# MGT_Banks_115-116.net
KiCad netlist of a schematic drawn in Altium Designer
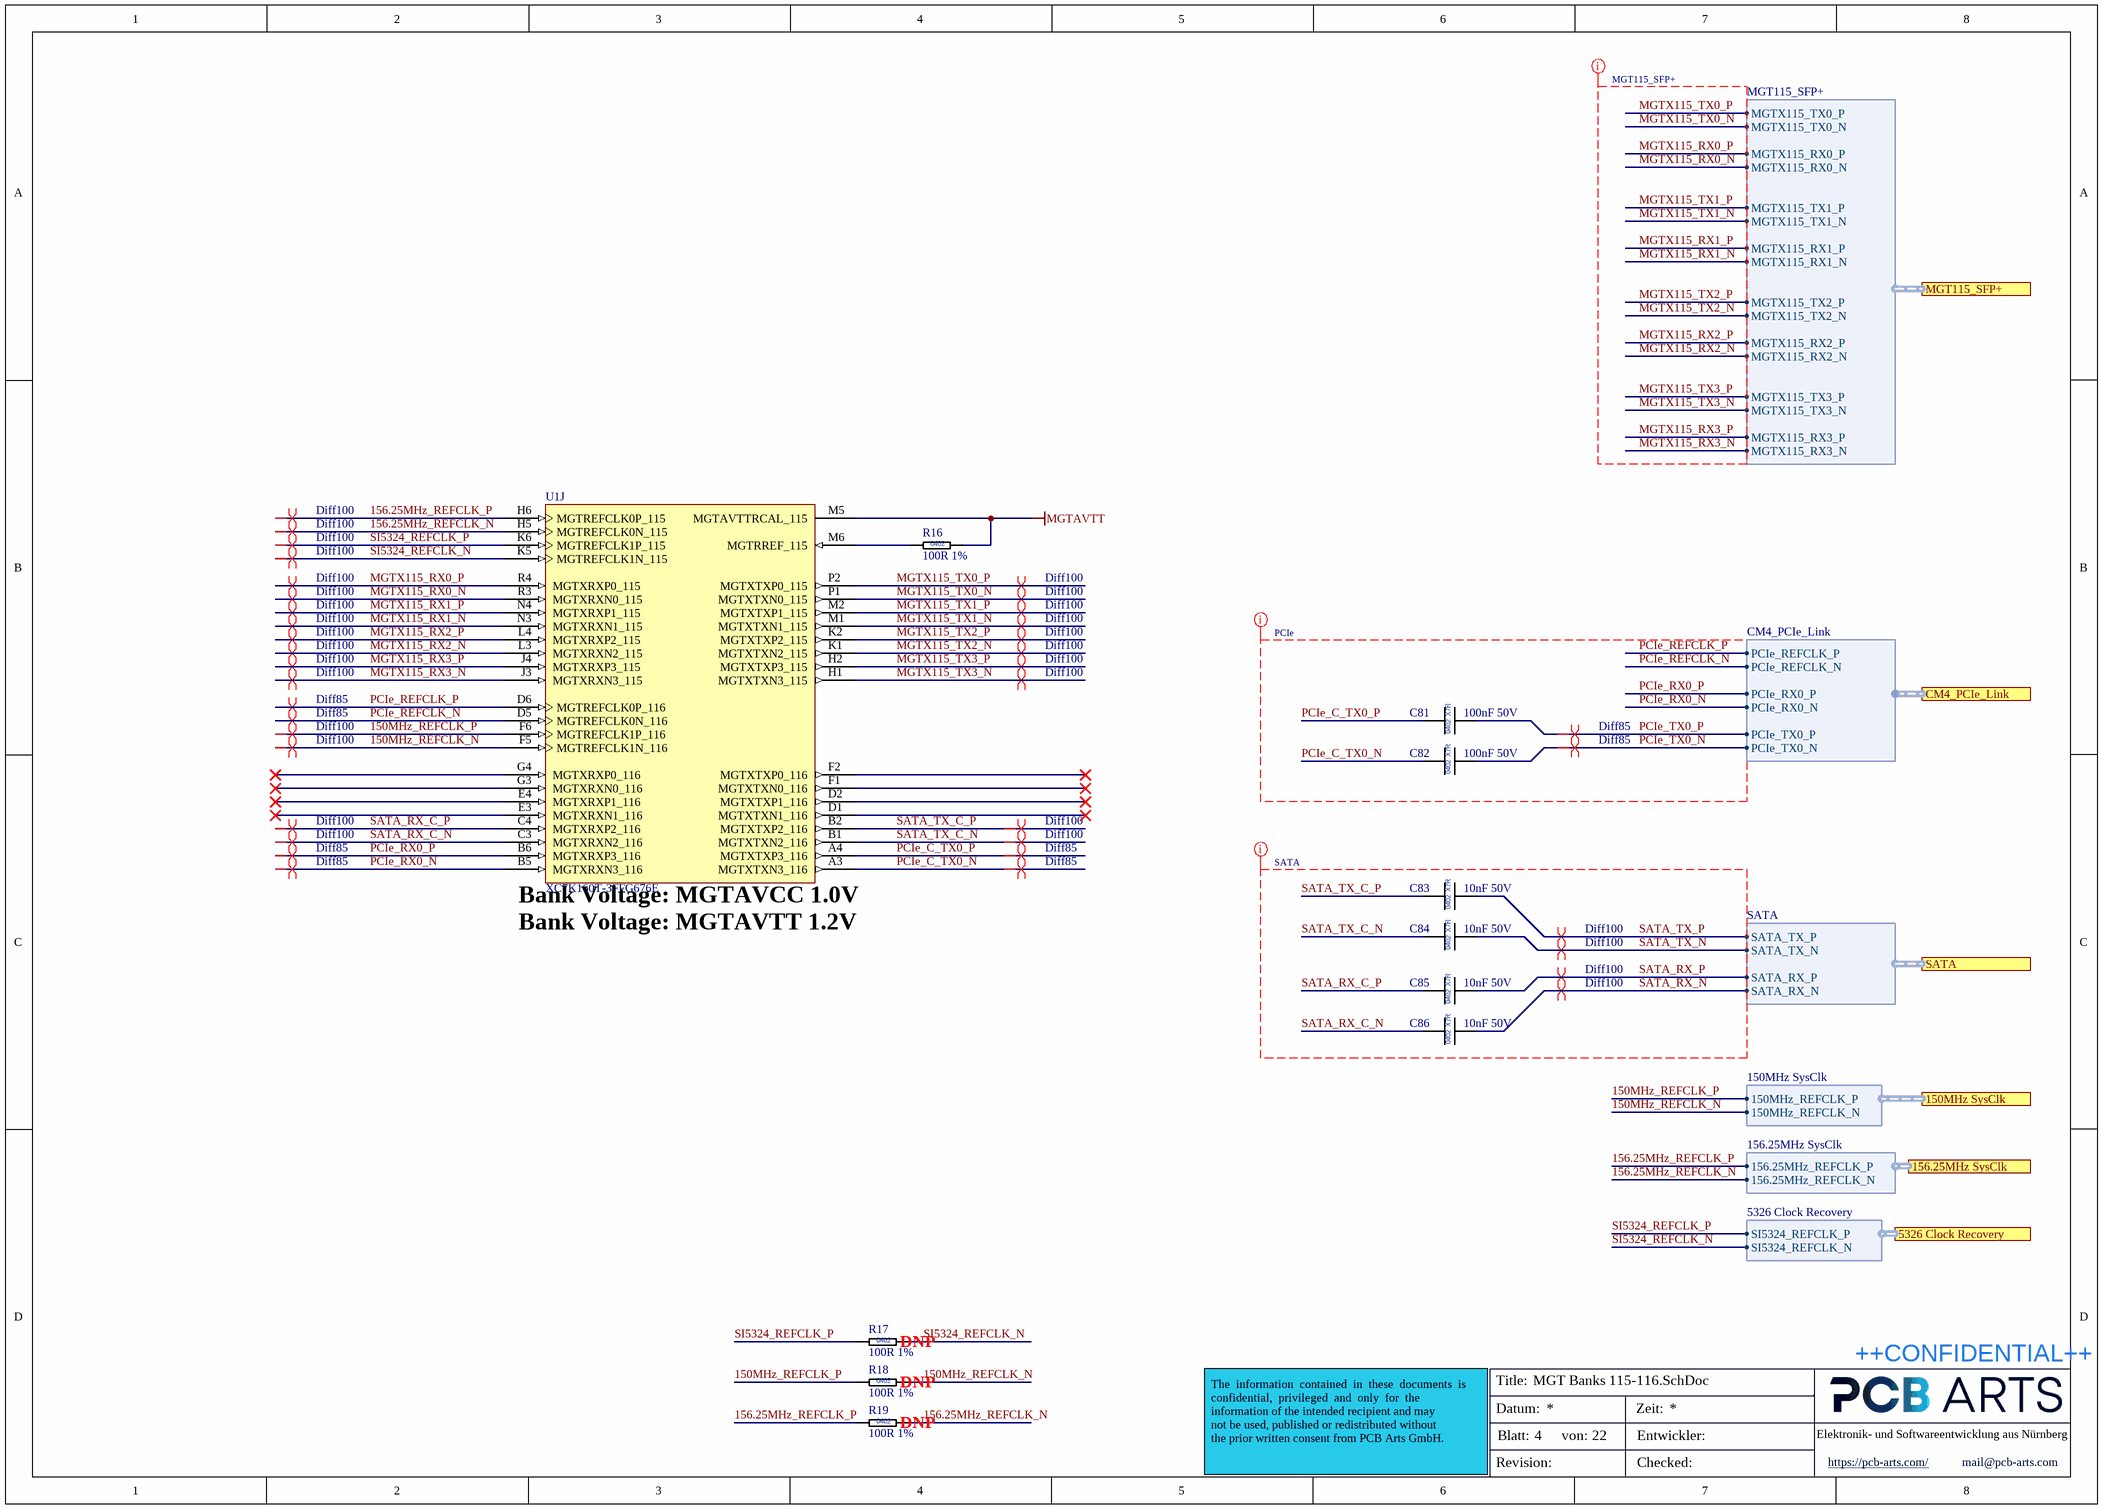
[diagram p0: MGT Banks 115-116.SchDoc]

(export (version "E")
  (design (tool "Eeschema 10.0.6"))
  (components
    (comp (ref "C81")
      (value "100nF 50V")
      (footprint "Cap:CAP_0402_L")
      (description "Multilayer Ceramic Capacitors MLCC - SMD/SMT 0402 50VDC")
      (libsource (lib "Cap") (part "CAP_0402_100nF_50V"))
    )
    (comp (ref "C82")
      (value "100nF 50V")
      (footprint "Cap:CAP_0402_L")
      (description "Multilayer Ceramic Capacitors MLCC - SMD/SMT 0402 50VDC")
      (libsource (lib "Cap") (part "CAP_0402_100nF_50V"))
    )
    (comp (ref "C83")
      (value "10nF 50V")
      (footprint "Cap:CAP_0402_L")
      (description "Multilayer Ceramic Capacitors MLCC - SMD/SMT 0402 50VDC")
      (libsource (lib "Cap") (part "CAP_0402_10nF_50V"))
    )
    (comp (ref "C84")
      (value "10nF 50V")
      (footprint "Cap:CAP_0402_L")
      (description "Multilayer Ceramic Capacitors MLCC - SMD/SMT 0402 50VDC")
      (libsource (lib "Cap") (part "CAP_0402_10nF_50V"))
    )
    (comp (ref "C85")
      (value "10nF 50V")
      (footprint "Cap:CAP_0402_L")
      (description "Multilayer Ceramic Capacitors MLCC - SMD/SMT 0402 50VDC")
      (libsource (lib "Cap") (part "CAP_0402_10nF_50V"))
    )
    (comp (ref "C86")
      (value "10nF 50V")
      (footprint "Cap:CAP_0402_L")
      (description "Multilayer Ceramic Capacitors MLCC - SMD/SMT 0402 50VDC")
      (libsource (lib "Cap") (part "CAP_0402_10nF_50V"))
    )
    (comp (ref "R16")
      (value "100R 1%")
      (footprint "Res:RES_0402_L")
      (description "Thick Film Resistors - SMD 100Ohm 1%")
      (libsource (lib "Res") (part "RES_0402_100R_1%"))
    )
    (comp (ref "R17")
      (value "100R 1%")
      (footprint "Res:RES_0402_L")
      (description "Thick Film Resistors - SMD 100Ohm 1%")
      (libsource (lib "Res") (part "RES_0402_100R_1%"))
    )
    (comp (ref "R18")
      (value "100R 1%")
      (footprint "Res:RES_0402_L")
      (description "Thick Film Resistors - SMD 100Ohm 1%")
      (libsource (lib "Res") (part "RES_0402_100R_1%"))
    )
    (comp (ref "R19")
      (value "100R 1%")
      (footprint "Res:RES_0402_L")
      (description "Thick Film Resistors - SMD 100Ohm 1%")
      (libsource (lib "Res") (part "RES_0402_100R_1%"))
    )
    (comp (ref "U1")
      (value "XC7K160T-3FFG676E")
      (footprint "Digital:BGA100P2700X2700X317-676N")
      (description "Kintex-7 FPGA, 400 User I/Os, 8 GTX, 676-Ball BGA, Speed Grade 3, Extended Grade, Pb-Free")
      (libsource (lib "Digital") (part "XC7K160T-3FFG676E_Kintex-7 FPGA, 400 User I/Os, 8 GTX, FFG676"))
    )
  )
  (nets
    (net (code "10") (name "/150MHz_REFCLK_N") (class "Default")
      (node (ref "R18") (pin "2") (pinfunction "2_2") (pintype "passive"))
      (node (ref "U1") (pin "F5") (pinfunction "MGTREFCLK1N_116_F5") (pintype "input"))
    )
    (net (code "11") (name "/150MHz_REFCLK_P") (class "Default")
      (node (ref "R18") (pin "1") (pinfunction "1_1") (pintype "passive"))
      (node (ref "U1") (pin "F6") (pinfunction "MGTREFCLK1P_116_F6") (pintype "input"))
    )
    (net (code "12") (name "/156.25MHz_REFCLK_N") (class "Default")
      (node (ref "R19") (pin "2") (pinfunction "2_2") (pintype "passive"))
      (node (ref "U1") (pin "H5") (pinfunction "MGTREFCLK0N_115_H5") (pintype "input"))
    )
    (net (code "13") (name "/156.25MHz_REFCLK_P") (class "Default")
      (node (ref "R19") (pin "1") (pinfunction "1_1") (pintype "passive"))
      (node (ref "U1") (pin "H6") (pinfunction "MGTREFCLK0P_115_H6") (pintype "input"))
    )
    (net (code "14") (name "/MGTX115_RX0_N") (class "Default")
      (node (ref "U1") (pin "R3") (pinfunction "MGTXRXN0_115_R3") (pintype "input"))
    )
    (net (code "15") (name "/MGTX115_RX0_P") (class "Default")
      (node (ref "U1") (pin "R4") (pinfunction "MGTXRXP0_115_R4") (pintype "input"))
    )
    (net (code "16") (name "/MGTX115_RX1_N") (class "Default")
      (node (ref "U1") (pin "N3") (pinfunction "MGTXRXN1_115_N3") (pintype "input"))
    )
    (net (code "17") (name "/MGTX115_RX1_P") (class "Default")
      (node (ref "U1") (pin "N4") (pinfunction "MGTXRXP1_115_N4") (pintype "input"))
    )
    (net (code "18") (name "/MGTX115_RX2_N") (class "Default")
      (node (ref "U1") (pin "L3") (pinfunction "MGTXRXN2_115_L3") (pintype "input"))
    )
    (net (code "19") (name "/MGTX115_RX2_P") (class "Default")
      (node (ref "U1") (pin "L4") (pinfunction "MGTXRXP2_115_L4") (pintype "input"))
    )
    (net (code "20") (name "/MGTX115_RX3_N") (class "Default")
      (node (ref "U1") (pin "J3") (pinfunction "MGTXRXN3_115_J3") (pintype "input"))
    )
    (net (code "21") (name "/MGTX115_RX3_P") (class "Default")
      (node (ref "U1") (pin "J4") (pinfunction "MGTXRXP3_115_J4") (pintype "input"))
    )
    (net (code "22") (name "/MGTX115_TX0_N") (class "Default")
      (node (ref "U1") (pin "P1") (pinfunction "MGTXTXN0_115_P1") (pintype "output"))
    )
    (net (code "23") (name "/MGTX115_TX0_P") (class "Default")
      (node (ref "U1") (pin "P2") (pinfunction "MGTXTXP0_115_P2") (pintype "output"))
    )
    (net (code "24") (name "/MGTX115_TX1_N") (class "Default")
      (node (ref "U1") (pin "M1") (pinfunction "MGTXTXN1_115_M1") (pintype "output"))
    )
    (net (code "25") (name "/MGTX115_TX1_P") (class "Default")
      (node (ref "U1") (pin "M2") (pinfunction "MGTXTXP1_115_M2") (pintype "output"))
    )
    (net (code "26") (name "/MGTX115_TX2_N") (class "Default")
      (node (ref "U1") (pin "K1") (pinfunction "MGTXTXN2_115_K1") (pintype "output"))
    )
    (net (code "27") (name "/MGTX115_TX2_P") (class "Default")
      (node (ref "U1") (pin "K2") (pinfunction "MGTXTXP2_115_K2") (pintype "output"))
    )
    (net (code "28") (name "/MGTX115_TX3_N") (class "Default")
      (node (ref "U1") (pin "H1") (pinfunction "MGTXTXN3_115_H1") (pintype "output"))
    )
    (net (code "29") (name "/MGTX115_TX3_P") (class "Default")
      (node (ref "U1") (pin "H2") (pinfunction "MGTXTXP3_115_H2") (pintype "output"))
    )
    (net (code "30") (name "/PCIe_C_TX0_N") (class "Default")
      (node (ref "C82") (pin "1") (pinfunction "1_1") (pintype "passive"))
      (node (ref "U1") (pin "A3") (pinfunction "MGTXTXN3_116_A3") (pintype "output"))
    )
    (net (code "31") (name "/PCIe_C_TX0_P") (class "Default")
      (node (ref "C81") (pin "1") (pinfunction "1_1") (pintype "passive"))
      (node (ref "U1") (pin "A4") (pinfunction "MGTXTXP3_116_A4") (pintype "output"))
    )
    (net (code "32") (name "/PCIe_REFCLK_N") (class "Default")
      (node (ref "U1") (pin "D5") (pinfunction "MGTREFCLK0N_116_D5") (pintype "input"))
    )
    (net (code "33") (name "/PCIe_REFCLK_P") (class "Default")
      (node (ref "U1") (pin "D6") (pinfunction "MGTREFCLK0P_116_D6") (pintype "input"))
    )
    (net (code "34") (name "/PCIe_RX0_N") (class "Default")
      (node (ref "U1") (pin "B5") (pinfunction "MGTXRXN3_116_B5") (pintype "input"))
    )
    (net (code "35") (name "/PCIe_RX0_P") (class "Default")
      (node (ref "U1") (pin "B6") (pinfunction "MGTXRXP3_116_B6") (pintype "input"))
    )
    (net (code "36") (name "/PCIe_TX0_N") (class "Default")
      (node (ref "C82") (pin "2") (pinfunction "2_2") (pintype "passive"))
    )
    (net (code "37") (name "/PCIe_TX0_P") (class "Default")
      (node (ref "C81") (pin "2") (pinfunction "2_2") (pintype "passive"))
    )
    (net (code "38") (name "/SATA_RX_C_N") (class "Default")
      (node (ref "C86") (pin "1") (pinfunction "1_1") (pintype "passive"))
      (node (ref "U1") (pin "C3") (pinfunction "MGTXRXN2_116_C3") (pintype "input"))
    )
    (net (code "39") (name "/SATA_RX_C_P") (class "Default")
      (node (ref "C85") (pin "1") (pinfunction "1_1") (pintype "passive"))
      (node (ref "U1") (pin "C4") (pinfunction "MGTXRXP2_116_C4") (pintype "input"))
    )
    (net (code "40") (name "/SATA_RX_N") (class "Default")
      (node (ref "C86") (pin "2") (pinfunction "2_2") (pintype "passive"))
    )
    (net (code "41") (name "/SATA_RX_P") (class "Default")
      (node (ref "C85") (pin "2") (pinfunction "2_2") (pintype "passive"))
    )
    (net (code "42") (name "/SATA_TX_C_N") (class "Default")
      (node (ref "C84") (pin "1") (pinfunction "1_1") (pintype "passive"))
      (node (ref "U1") (pin "B1") (pinfunction "MGTXTXN2_116_B1") (pintype "output"))
    )
    (net (code "43") (name "/SATA_TX_C_P") (class "Default")
      (node (ref "C83") (pin "1") (pinfunction "1_1") (pintype "passive"))
      (node (ref "U1") (pin "B2") (pinfunction "MGTXTXP2_116_B2") (pintype "output"))
    )
    (net (code "44") (name "/SATA_TX_N") (class "Default")
      (node (ref "C84") (pin "2") (pinfunction "2_2") (pintype "passive"))
    )
    (net (code "45") (name "/SATA_TX_P") (class "Default")
      (node (ref "C83") (pin "2") (pinfunction "2_2") (pintype "passive"))
    )
    (net (code "46") (name "/SI5324_REFCLK_N") (class "Default")
      (node (ref "R17") (pin "2") (pinfunction "2_2") (pintype "passive"))
      (node (ref "U1") (pin "K5") (pinfunction "MGTREFCLK1N_115_K5") (pintype "input"))
    )
    (net (code "47") (name "/SI5324_REFCLK_P") (class "Default")
      (node (ref "R17") (pin "1") (pinfunction "1_1") (pintype "passive"))
      (node (ref "U1") (pin "K6") (pinfunction "MGTREFCLK1P_115_K6") (pintype "input"))
    )
    (net (code "54") (name "MGTAVTT") (class "Default")
      (node (ref "R16") (pin "2") (pinfunction "2_2") (pintype "passive"))
      (node (ref "U1") (pin "M5") (pinfunction "MGTAVTTRCAL_115_M5") (pintype "passive"))
    )
    (net (code "55") (name "Net-(U1J-MGTRREF_115)") (class "Default")
      (node (ref "R16") (pin "1") (pinfunction "1_1") (pintype "passive"))
      (node (ref "U1") (pin "M6") (pinfunction "MGTRREF_115_M6") (pintype "input"))
    )
    (net (code "56") (name "unconnected-(U1J-MGTXRXN0_116-PadG3)") (class "Default")
      (node (ref "U1") (pin "G3") (pinfunction "MGTXRXN0_116_G3") (pintype "input+no_connect"))
    )
    (net (code "57") (name "unconnected-(U1J-MGTXRXN1_116-PadE3)") (class "Default")
      (node (ref "U1") (pin "E3") (pinfunction "MGTXRXN1_116_E3") (pintype "input+no_connect"))
    )
    (net (code "58") (name "unconnected-(U1J-MGTXRXP0_116-PadG4)") (class "Default")
      (node (ref "U1") (pin "G4") (pinfunction "MGTXRXP0_116_G4") (pintype "input+no_connect"))
    )
    (net (code "59") (name "unconnected-(U1J-MGTXRXP1_116-PadE4)") (class "Default")
      (node (ref "U1") (pin "E4") (pinfunction "MGTXRXP1_116_E4") (pintype "input+no_connect"))
    )
    (net (code "60") (name "unconnected-(U1J-MGTXTXN0_116-PadF1)") (class "Default")
      (node (ref "U1") (pin "F1") (pinfunction "MGTXTXN0_116_F1") (pintype "output+no_connect"))
    )
    (net (code "61") (name "unconnected-(U1J-MGTXTXN1_116-PadD1)") (class "Default")
      (node (ref "U1") (pin "D1") (pinfunction "MGTXTXN1_116_D1") (pintype "output+no_connect"))
    )
    (net (code "62") (name "unconnected-(U1J-MGTXTXP0_116-PadF2)") (class "Default")
      (node (ref "U1") (pin "F2") (pinfunction "MGTXTXP0_116_F2") (pintype "output+no_connect"))
    )
    (net (code "63") (name "unconnected-(U1J-MGTXTXP1_116-PadD2)") (class "Default")
      (node (ref "U1") (pin "D2") (pinfunction "MGTXTXP1_116_D2") (pintype "output+no_connect"))
    )
  )
)
